# Clock_bord.net
KiCad netlist of a schematic drawn in Altium Designer
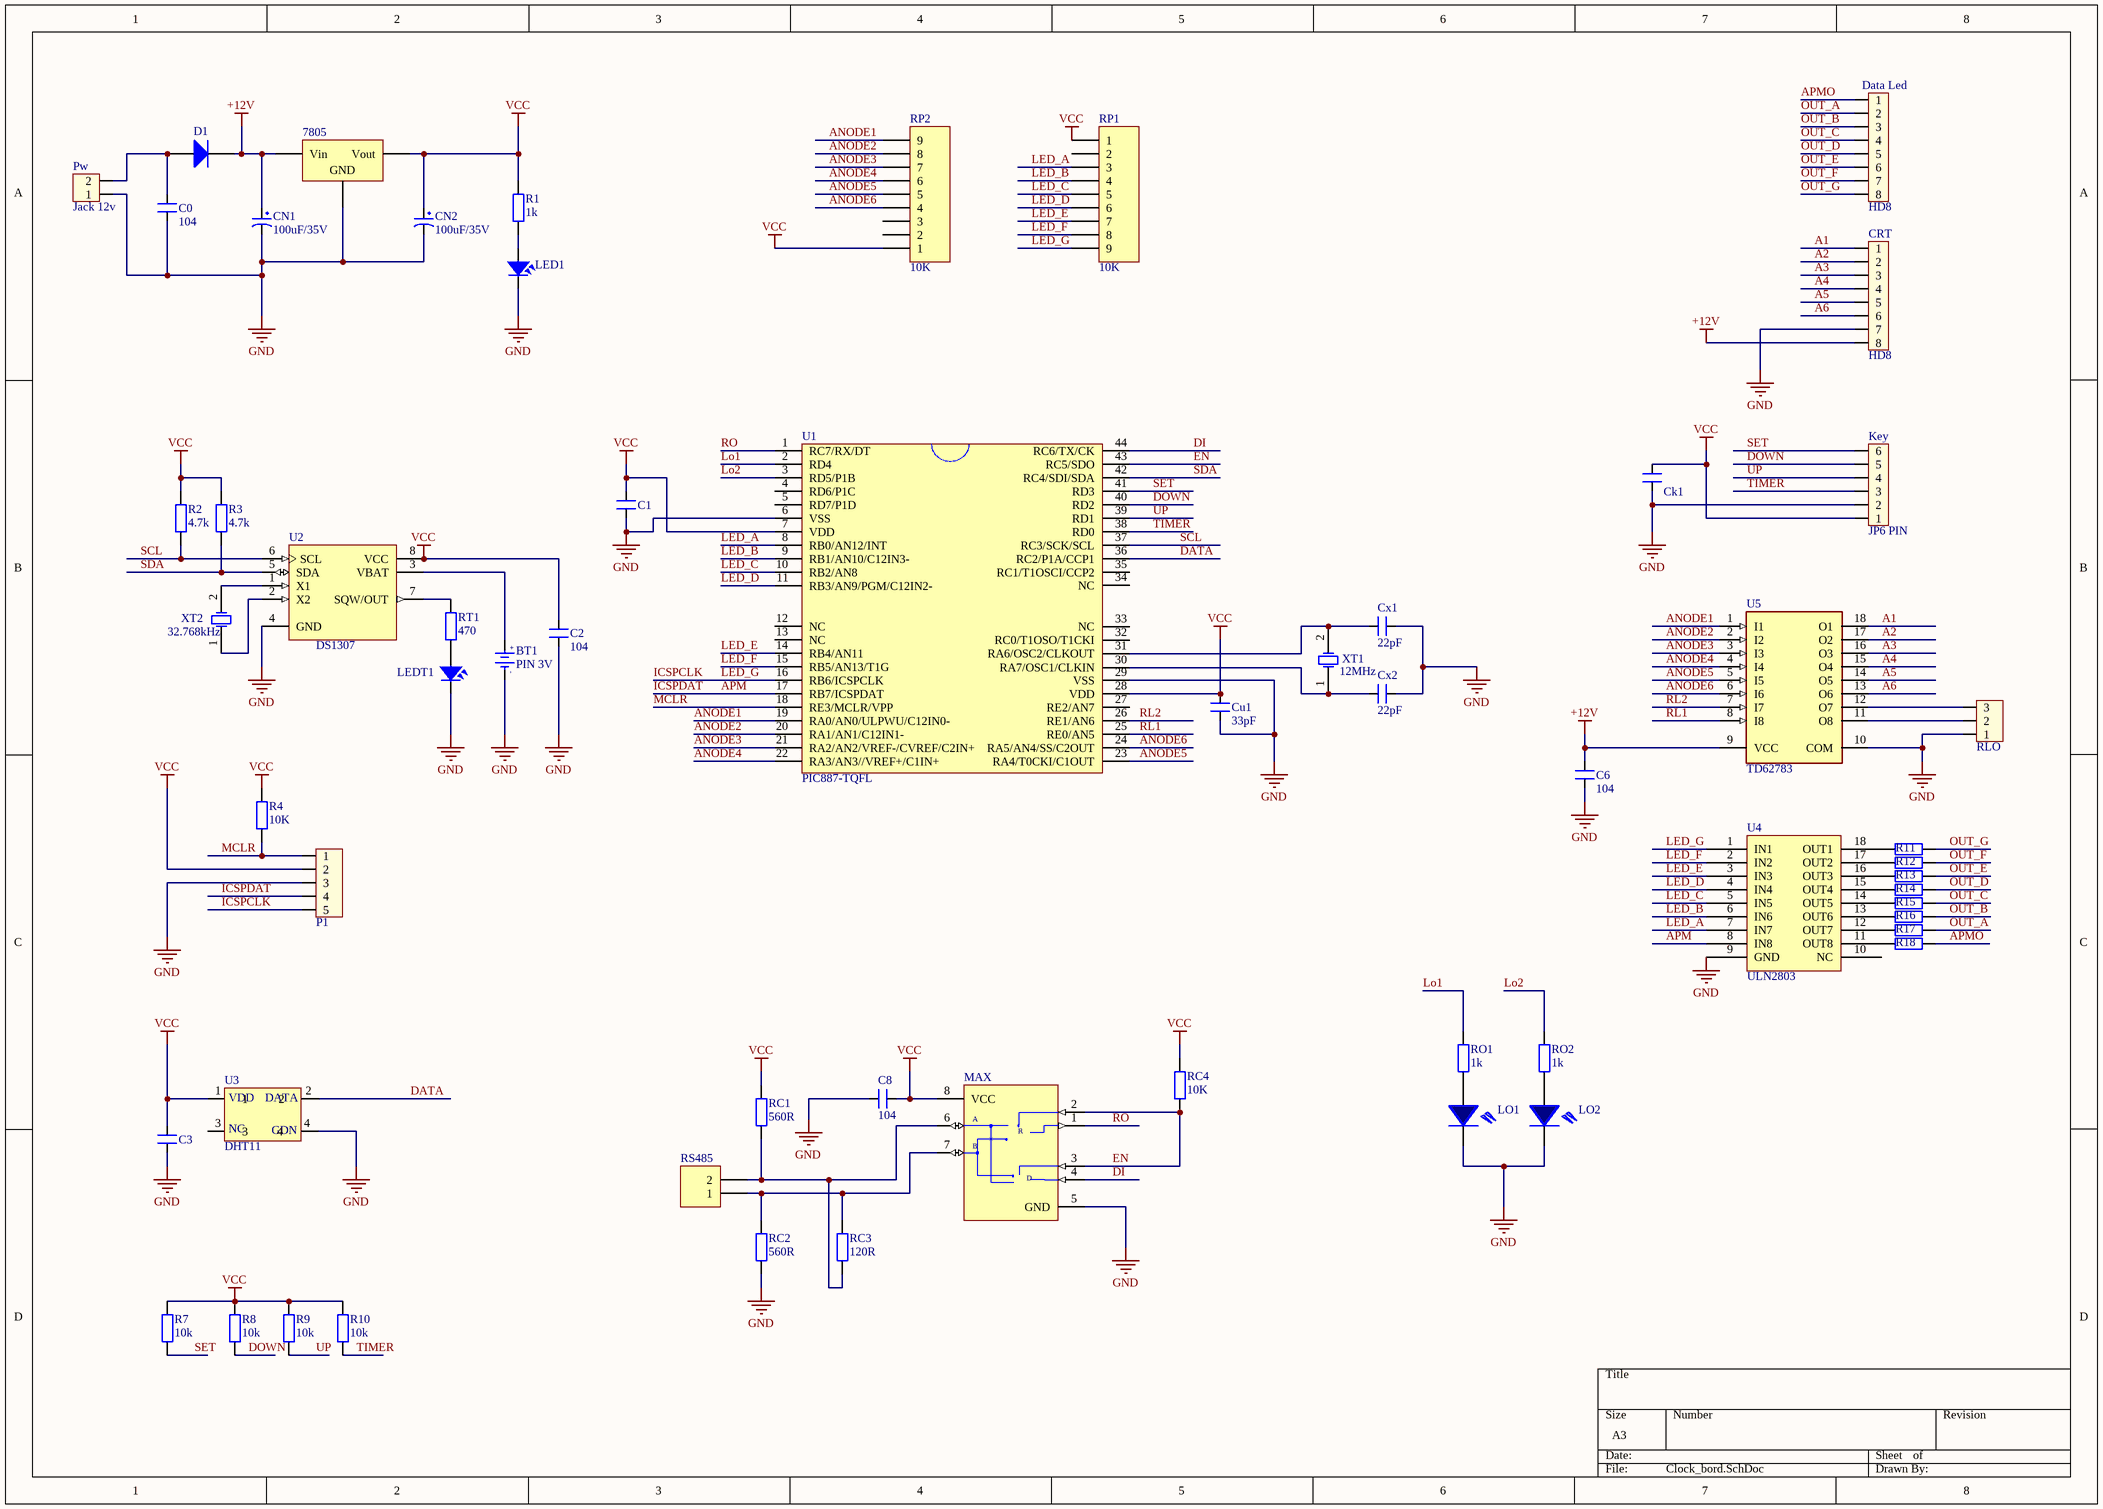
[diagram p0: Clock_bord.SchDoc]

(export (version "E")
  (design (tool "Eeschema 10.0.6"))
  (components
    (comp (ref "7805")
      (value "Volt Reg")
      (footprint "TO-263")
      (description "Voltage Regulator")
      (fields (field (name "PUBLISHER") "Altium Limited"))
      (libsource (lib "Miscellaneous Devices") (part "Volt Reg"))
    )
    (comp (ref "BT1")
      (value "PIN 3V")
      (footprint "Duy_PCB Library:PIN3V")
      (description "Battery 3VDC")
      (libsource (lib "Duy_Schematic") (part "PIN 3V"))
    )
    (comp (ref "C0")
      (value "104")
      (footprint "Duy_PCB Library:CN2")
      (description "Cap np Cremic Value  104pF => 105pF")
      (libsource (lib "Duy_Schematic") (part "CN2"))
    )
    (comp (ref "C1")
      (value "104")
      (footprint "CN1")
      (description "Cap np Cremic Value  104pF => 105pF")
      (libsource (lib "Duy_Schematic") (part "CN2"))
    )
    (comp (ref "C2")
      (value "104")
      (footprint "CN1")
      (description "Cap np Cremic Value  104pF => 105pF")
      (libsource (lib "Duy_Schematic") (part "CN2"))
    )
    (comp (ref "C3")
      (value "104")
      (footprint "CN1")
      (description "Cap np Cremic Value  104pF => 105pF")
      (libsource (lib "Duy_Schematic") (part "CN2"))
    )
    (comp (ref "C6")
      (value "104")
      (footprint "CN1")
      (description "Cap np Cremic Value  104pF => 105pF")
      (libsource (lib "Duy_Schematic") (part "CN2"))
    )
    (comp (ref "C8")
      (value "104")
      (footprint "CN1")
      (description "Cap np Cremic Value  1pF => 472 pF")
      (libsource (lib "Duy_Schematic") (part "CN1"))
    )
    (comp (ref "Ck1")
      (value "100pF")
      (footprint "SM-1206")
      (description "Cap np Cremic Value  1pF => 472 pF")
      (libsource (lib "Duy_Schematic") (part "CN1"))
    )
    (comp (ref "CN1")
      (value "100uF/35V")
      (footprint "CP1.5/3.4")
      (description "Cap 100uF/35V - 470uF/16V")
      (libsource (lib "Duy_Schematic") (part "CP3"))
    )
    (comp (ref "CN2")
      (value "100uF/35V")
      (footprint "CP1.5/3.4")
      (description "Cap 100uF/35V - 470uF/16V")
      (libsource (lib "Duy_Schematic") (part "CP3"))
    )
    (comp (ref "CRT")
      (value "HD8")
      (footprint "HED8")
      (description "Hedear 8")
      (fields (field (name "CREAT BY") "VanDungEvn@Gmail.com"))
      (libsource (lib "Duy_Schematic") (part "Hed8"))
    )
    (comp (ref "Cu1")
      (value "33pF")
      (footprint "SM-0805")
      (description "Cap np Cremic value 1pF => 100pF")
      (libsource (lib "Duy_Schematic") (part "CN0"))
    )
    (comp (ref "Cx1")
      (value "22pF")
      (footprint "CN1")
      (description "Cap np Cremic value 1pF => 100pF")
      (libsource (lib "Duy_Schematic") (part "CN0"))
    )
    (comp (ref "Cx2")
      (value "22pF")
      (footprint "CN1")
      (description "Cap np Cremic value 1pF => 100pF")
      (libsource (lib "Duy_Schematic") (part "CN0"))
    )
    (comp (ref "D1")
      (value "Diode 1N4007")
      (footprint "Duy_PCB Library:D1A")
      (description "1 Amp General Purpose Rectifier")
      (fields (field (name "PUBLISHER") "Altium Limited"))
      (libsource (lib "Miscellaneous Devices") (part "Diode 1N4007"))
    )
    (comp (ref "Data Led")
      (value "HD8")
      (footprint "HED8")
      (description "Hedear 8")
      (fields (field (name "CREAT BY") "VanDungEvn@Gmail.com"))
      (libsource (lib "Duy_Schematic") (part "Hed8"))
    )
    (comp (ref "Key") (value "JP6 PIN") (footprint "JP6") (libsource (lib "Duy_Schematic") (part "JP6")))
    (comp (ref "LED1")
      (value "LED")
      (footprint "SM-1206")
      (description "Led  Vuong")
      (libsource (lib "") (part "LED_1"))
    )
    (comp (ref "LEDT1")
      (value "LED")
      (footprint "SM-1206")
      (description "Led  Vuong")
      (libsource (lib "") (part "LED_1"))
    )
    (comp (ref "LO1")
      (value "LED")
      (footprint "SM-1206")
      (description "Led  Vuong")
      (libsource (lib "Duy_Schematic") (part "LED"))
    )
    (comp (ref "LO2")
      (value "LED")
      (footprint "SM-1206")
      (description "Led  Vuong")
      (libsource (lib "Duy_Schematic") (part "LED"))
    )
    (comp (ref "MAX")
      (value "MAX485CSA")
      (footprint "DIP8/W0.3")
      (description "Low-Power, Slew-Rate-Limited RS-485/RS-422 Transceiver")
      (fields (field (name "PUBLISHER") "Altium Limited"))
      (libsource (lib "Maxim Communication Transceiver") (part "MAX485CSA"))
    )
    (comp (ref "P1")
      (value "JP5")
      (footprint "CON5")
      (description "Connector 5")
      (libsource (lib "Duy_Schematic") (part "Con5"))
    )
    (comp (ref "Pw")
      (value "Jack 12v")
      (footprint "HED2")
      (description "Header 2 (Green)")
      (libsource (lib "Duy_Schematic") (part "Hed2"))
    )
    (comp (ref "R1")
      (value "1k")
      (footprint "SM-1206")
      (description "Resistor 1/4W")
      (libsource (lib "Duy_Schematic") (part "R1/4W"))
    )
    (comp (ref "R2")
      (value "4.7k")
      (footprint "R1/4W")
      (description "Resistor 1/4W")
      (libsource (lib "Duy_Schematic") (part "R1/4W"))
    )
    (comp (ref "R3")
      (value "4.7k")
      (footprint "R1/4W")
      (description "Resistor 1/4W")
      (libsource (lib "Duy_Schematic") (part "R1/4W"))
    )
    (comp (ref "R4")
      (value "10K")
      (footprint "R1/4W")
      (description "Resistor 1/4W")
      (libsource (lib "Duy_Schematic") (part "R1/4W"))
    )
    (comp (ref "R7")
      (value "10k")
      (footprint "R1/4W")
      (description "Resistor 1/4W")
      (libsource (lib "Duy_Schematic") (part "R1/4W"))
    )
    (comp (ref "R8")
      (value "10k")
      (footprint "R1/4W")
      (description "Resistor 1/4W")
      (libsource (lib "Duy_Schematic") (part "R1/4W"))
    )
    (comp (ref "R9")
      (value "10k")
      (footprint "R1/4W")
      (description "Resistor 1/4W")
      (libsource (lib "Duy_Schematic") (part "R1/4W"))
    )
    (comp (ref "R10")
      (value "10k")
      (footprint "R1/4W")
      (description "Resistor 1/4W")
      (libsource (lib "Duy_Schematic") (part "R1/4W"))
    )
    (comp (ref "R11")
      (value "220R")
      (footprint "SM-1206")
      (description "Resistor 1/4W")
      (libsource (lib "Duy_Schematic") (part "R1/4W"))
    )
    (comp (ref "R12")
      (value "220R")
      (footprint "SM-1206")
      (description "Resistor 1/4W")
      (libsource (lib "Duy_Schematic") (part "R1/4W"))
    )
    (comp (ref "R13")
      (value "220R")
      (footprint "SM-1206")
      (description "Resistor 1/4W")
      (libsource (lib "Duy_Schematic") (part "R1/4W"))
    )
    (comp (ref "R14")
      (value "220R")
      (footprint "SM-1206")
      (description "Resistor 1/4W")
      (libsource (lib "Duy_Schematic") (part "R1/4W"))
    )
    (comp (ref "R15")
      (value "220R")
      (footprint "SM-1206")
      (description "Resistor 1/4W")
      (libsource (lib "Duy_Schematic") (part "R1/4W"))
    )
    (comp (ref "R16")
      (value "220R")
      (footprint "SM-1206")
      (description "Resistor 1/4W")
      (libsource (lib "Duy_Schematic") (part "R1/4W"))
    )
    (comp (ref "R17")
      (value "220R")
      (footprint "SM-1206")
      (description "Resistor 1/4W")
      (libsource (lib "Duy_Schematic") (part "R1/4W"))
    )
    (comp (ref "R18")
      (value "220R")
      (footprint "SM-1206")
      (description "Resistor 1/4W")
      (libsource (lib "Duy_Schematic") (part "R1/4W"))
    )
    (comp (ref "RC1")
      (value "560R")
      (footprint "R1/4W")
      (description "Resistor 1/4W")
      (libsource (lib "Duy_Schematic") (part "R1/4W"))
    )
    (comp (ref "RC2")
      (value "560R")
      (footprint "R1/4W")
      (description "Resistor 1/4W")
      (libsource (lib "Duy_Schematic") (part "R1/4W"))
    )
    (comp (ref "RC3")
      (value "120R")
      (footprint "SM-1206")
      (description "Resistor 1/4W")
      (libsource (lib "Duy_Schematic") (part "R1/4W"))
    )
    (comp (ref "RC4")
      (value "10K")
      (footprint "R1/4W")
      (description "Resistor 1/4W")
      (libsource (lib "Duy_Schematic") (part "R1/4W"))
    )
    (comp (ref "RLO")
      (value "JP3")
      (footprint "CON3")
      (description "Connector 3")
      (libsource (lib "Duy_Schematic") (part "Con3"))
    )
    (comp (ref "RO1")
      (value "1k")
      (footprint "SM-1206")
      (description "Resistor 1/4W")
      (libsource (lib "Duy_Schematic") (part "R1/4W"))
    )
    (comp (ref "RO2")
      (value "1k")
      (footprint "SM-1206")
      (description "Resistor 1/4W")
      (libsource (lib "Duy_Schematic") (part "R1/4W"))
    )
    (comp (ref "RP1")
      (value "10K")
      (footprint "RN8")
      (description "Header, 9-Pin")
      (fields (field (name "PUBLISHER") "Altium Limited"))
      (libsource (lib "") (part "Header 9_1"))
    )
    (comp (ref "RP2")
      (value "10K")
      (footprint "RN8")
      (description "Header, 9-Pin")
      (fields (field (name "PUBLISHER") "Altium Limited"))
      (libsource (lib "Miscellaneous Connectors") (part "Header 9"))
    )
    (comp (ref "RS485")
      (value "Header 2")
      (footprint "CON2")
      (description "Header, 2-Pin")
      (fields (field (name "PUBLISHER") "Altium Limited"))
      (libsource (lib "Miscellaneous Connectors") (part "Header 2"))
    )
    (comp (ref "RT1")
      (value "470")
      (footprint "SM-1206")
      (description "Resistor 1/4W")
      (libsource (lib "Duy_Schematic") (part "R1/4W"))
    )
    (comp (ref "U1")
      (value "PIC887-TQFL")
      (footprint "TQFP-44")
      (description "16F887_TQFP")
      (libsource (lib "Duy_Schematic") (part "PIC16F887-TQFL"))
    )
    (comp (ref "U2")
      (value "DS1307")
      (footprint "DIP8/W0.3")
      (description "64 X 8 Serial Real-Time Clock")
      (fields (field (name "PUBLISHER") "Altium Limited"))
      (libsource (lib "Dallas Peripheral Real Time Clock") (part "DS1307"))
    )
    (comp (ref "U3")
      (value "DHT11")
      (footprint "CON4")
      (description "Sensor Ther")
      (libsource (lib "Duy_Schematic") (part "DHT11"))
    )
    (comp (ref "U4") (value "ULN2803") (footprint "ULN2803") (libsource (lib "Device") (part "ULN 2803")))
    (comp (ref "U5")
      (value "TD62783")
      (footprint "ULN2803")
      (libsource (lib "Duy_Schematic") (part "TD62783AF"))
    )
    (comp (ref "XT1")
      (value "12MHz")
      (footprint "Xtal_SMD")
      (description "Crystal Oscillator")
      (fields (field (name "PUBLISHER") "Altium Limited"))
      (libsource (lib "Miscellaneous Devices") (part "XTAL"))
    )
    (comp (ref "XT2")
      (value "32.768kHz")
      (footprint "Device:tu_gom")
      (description "Crystal Oscillator")
      (fields (field (name "PUBLISHER") "Altium Limited"))
      (libsource (lib "Miscellaneous Devices") (part "XTAL"))
    )
  )
  (nets
    (net (code "1") (name "+12V") (class "Default")
      (node (ref "7805") (pin "1") (pinfunction "Vin_1") (pintype "passive"))
      (node (ref "C6") (pin "2") (pinfunction "2_2") (pintype "passive"))
      (node (ref "CN1") (pin "1") (pinfunction "1_1") (pintype "passive"))
      (node (ref "CRT") (pin "8") (pinfunction "8_8") (pintype "passive"))
      (node (ref "D1") (pin "2") (pinfunction "K_2") (pintype "passive"))
      (node (ref "U5") (pin "9") (pinfunction "VCC_9") (pintype "power_in"))
    )
    (net (code "2") (name "/A1") (class "Default")
      (node (ref "CRT") (pin "1") (pinfunction "1_1") (pintype "passive"))
      (node (ref "U5") (pin "18") (pinfunction "O1_18") (pintype "open_collector"))
    )
    (net (code "3") (name "/A2") (class "Default")
      (node (ref "CRT") (pin "2") (pinfunction "2_2") (pintype "passive"))
      (node (ref "U5") (pin "17") (pinfunction "O2_17") (pintype "open_collector"))
    )
    (net (code "4") (name "/A3") (class "Default")
      (node (ref "CRT") (pin "3") (pinfunction "3_3") (pintype "passive"))
      (node (ref "U5") (pin "16") (pinfunction "O3_16") (pintype "open_collector"))
    )
    (net (code "5") (name "/A4") (class "Default")
      (node (ref "CRT") (pin "4") (pinfunction "4_4") (pintype "passive"))
      (node (ref "U5") (pin "15") (pinfunction "O4_15") (pintype "open_collector"))
    )
    (net (code "6") (name "/A5") (class "Default")
      (node (ref "CRT") (pin "5") (pinfunction "5_5") (pintype "passive"))
      (node (ref "U5") (pin "14") (pinfunction "O5_14") (pintype "open_collector"))
    )
    (net (code "7") (name "/A6") (class "Default")
      (node (ref "CRT") (pin "6") (pinfunction "6_6") (pintype "passive"))
      (node (ref "U5") (pin "13") (pinfunction "O6_13") (pintype "open_collector"))
    )
    (net (code "8") (name "/ANODE1") (class "Default")
      (node (ref "RP2") (pin "9") (pinfunction "9_9") (pintype "passive"))
      (node (ref "U1") (pin "19") (pinfunction "RA0/AN0/ULPWU/C12IN0-_19") (pintype "passive"))
      (node (ref "U5") (pin "1") (pinfunction "I1_1") (pintype "input"))
    )
    (net (code "9") (name "/ANODE2") (class "Default")
      (node (ref "RP2") (pin "8") (pinfunction "8_8") (pintype "passive"))
      (node (ref "U1") (pin "20") (pinfunction "RA1/AN1/C12IN1-_20") (pintype "passive"))
      (node (ref "U5") (pin "2") (pinfunction "I2_2") (pintype "input"))
    )
    (net (code "10") (name "/ANODE3") (class "Default")
      (node (ref "RP2") (pin "7") (pinfunction "7_7") (pintype "passive"))
      (node (ref "U1") (pin "21") (pinfunction "RA2/AN2/VREF-/CVREF/C2IN+_21") (pintype "passive"))
      (node (ref "U5") (pin "3") (pinfunction "I3_3") (pintype "input"))
    )
    (net (code "11") (name "/ANODE4") (class "Default")
      (node (ref "RP2") (pin "6") (pinfunction "6_6") (pintype "passive"))
      (node (ref "U1") (pin "22") (pinfunction "RA3/AN3//VREF+/C1IN+_22") (pintype "passive"))
      (node (ref "U5") (pin "4") (pinfunction "I4_4") (pintype "input"))
    )
    (net (code "12") (name "/ANODE5") (class "Default")
      (node (ref "RP2") (pin "5") (pinfunction "5_5") (pintype "passive"))
      (node (ref "U1") (pin "23") (pinfunction "RA4/T0CKI/C1OUT_23") (pintype "passive"))
      (node (ref "U5") (pin "5") (pinfunction "I5_5") (pintype "input"))
    )
    (net (code "13") (name "/ANODE6") (class "Default")
      (node (ref "RP2") (pin "4") (pinfunction "4_4") (pintype "passive"))
      (node (ref "U1") (pin "24") (pinfunction "RA5/AN4/SS/C2OUT_24") (pintype "passive"))
      (node (ref "U5") (pin "6") (pinfunction "I6_6") (pintype "input"))
    )
    (net (code "14") (name "/APM") (class "Default")
      (node (ref "P1") (pin "4") (pinfunction "4_4") (pintype "passive"))
      (node (ref "U1") (pin "17") (pinfunction "RB7/ICSPDAT_17") (pintype "passive"))
      (node (ref "U4") (pin "8") (pinfunction "IN8_8") (pintype "passive"))
    )
    (net (code "15") (name "/APMO") (class "Default")
      (node (ref "Data Led") (pin "1") (pinfunction "1_1") (pintype "passive"))
      (node (ref "R18") (pin "2") (pinfunction "2_2") (pintype "passive"))
    )
    (net (code "16") (name "/DATA") (class "Default")
      (node (ref "U1") (pin "36") (pinfunction "RC2/P1A/CCP1_36") (pintype "passive"))
      (node (ref "U3") (pin "2") (pinfunction "2_2") (pintype "passive"))
    )
    (net (code "17") (name "/DI") (class "Default")
      (node (ref "MAX") (pin "4") (pinfunction "DI_4") (pintype "input"))
      (node (ref "U1") (pin "44") (pinfunction "RC6/TX/CK_44") (pintype "passive"))
    )
    (net (code "18") (name "/DOWN") (class "Default")
      (node (ref "Key") (pin "5") (pinfunction "5_5") (pintype "passive"))
      (node (ref "R8") (pin "1") (pinfunction "1_1") (pintype "passive"))
      (node (ref "U1") (pin "40") (pinfunction "RD2_40") (pintype "passive"))
    )
    (net (code "19") (name "/EN") (class "Default")
      (node (ref "MAX") (pin "2") (pinfunction "~{RE}_2") (pintype "input"))
      (node (ref "MAX") (pin "3") (pinfunction "DE_3") (pintype "input"))
      (node (ref "RC4") (pin "1") (pinfunction "1_1") (pintype "passive"))
      (node (ref "U1") (pin "43") (pinfunction "RC5/SDO_43") (pintype "passive"))
    )
    (net (code "20") (name "/ICSPCLK") (class "Default")
      (node (ref "P1") (pin "5") (pinfunction "5_5") (pintype "passive"))
      (node (ref "RP1") (pin "9") (pinfunction "9_9") (pintype "passive"))
      (node (ref "U1") (pin "16") (pinfunction "RB6/ICSPCLK_16") (pintype "passive"))
      (node (ref "U4") (pin "1") (pinfunction "IN1_1") (pintype "passive"))
    )
    (net (code "21") (name "/LED_A") (class "Default")
      (node (ref "RP1") (pin "3") (pinfunction "3_3") (pintype "passive"))
      (node (ref "U1") (pin "8") (pinfunction "RB0/AN12/INT_8") (pintype "passive"))
      (node (ref "U4") (pin "7") (pinfunction "IN7_7") (pintype "passive"))
    )
    (net (code "22") (name "/LED_B") (class "Default")
      (node (ref "RP1") (pin "4") (pinfunction "4_4") (pintype "passive"))
      (node (ref "U1") (pin "9") (pinfunction "RB1/AN10/C12IN3-_9") (pintype "passive"))
      (node (ref "U4") (pin "6") (pinfunction "IN6_6") (pintype "passive"))
    )
    (net (code "23") (name "/LED_C") (class "Default")
      (node (ref "RP1") (pin "5") (pinfunction "5_5") (pintype "passive"))
      (node (ref "U1") (pin "10") (pinfunction "RB2/AN8_10") (pintype "passive"))
      (node (ref "U4") (pin "5") (pinfunction "IN5_5") (pintype "passive"))
    )
    (net (code "24") (name "/LED_D") (class "Default")
      (node (ref "RP1") (pin "6") (pinfunction "6_6") (pintype "passive"))
      (node (ref "U1") (pin "11") (pinfunction "RB3/AN9/PGM/C12IN2-_11") (pintype "passive"))
      (node (ref "U4") (pin "4") (pinfunction "IN4_4") (pintype "passive"))
    )
    (net (code "25") (name "/LED_E") (class "Default")
      (node (ref "RP1") (pin "7") (pinfunction "7_7") (pintype "passive"))
      (node (ref "U1") (pin "14") (pinfunction "RB4/AN11_14") (pintype "passive"))
      (node (ref "U4") (pin "3") (pinfunction "IN3_3") (pintype "passive"))
    )
    (net (code "26") (name "/LED_F") (class "Default")
      (node (ref "RP1") (pin "8") (pinfunction "8_8") (pintype "passive"))
      (node (ref "U1") (pin "15") (pinfunction "RB5/AN13/T1G_15") (pintype "passive"))
      (node (ref "U4") (pin "2") (pinfunction "IN2_2") (pintype "passive"))
    )
    (net (code "27") (name "/Lo1") (class "Default")
      (node (ref "RO1") (pin "1") (pinfunction "1_1") (pintype "passive"))
      (node (ref "U1") (pin "2") (pinfunction "RD4_2") (pintype "passive"))
    )
    (net (code "28") (name "/Lo2") (class "Default")
      (node (ref "RO2") (pin "1") (pinfunction "1_1") (pintype "passive"))
      (node (ref "U1") (pin "3") (pinfunction "RD5/P1B_3") (pintype "passive"))
    )
    (net (code "29") (name "/MCLR") (class "Default")
      (node (ref "P1") (pin "1") (pinfunction "1_1") (pintype "passive"))
      (node (ref "R4") (pin "1") (pinfunction "1_1") (pintype "passive"))
      (node (ref "U1") (pin "18") (pinfunction "RE3/MCLR/VPP_18") (pintype "passive"))
    )
    (net (code "30") (name "/OUT_A") (class "Default")
      (node (ref "Data Led") (pin "2") (pinfunction "2_2") (pintype "passive"))
      (node (ref "R17") (pin "2") (pinfunction "2_2") (pintype "passive"))
    )
    (net (code "31") (name "/OUT_B") (class "Default")
      (node (ref "Data Led") (pin "3") (pinfunction "3_3") (pintype "passive"))
      (node (ref "R16") (pin "2") (pinfunction "2_2") (pintype "passive"))
    )
    (net (code "32") (name "/OUT_C") (class "Default")
      (node (ref "Data Led") (pin "4") (pinfunction "4_4") (pintype "passive"))
      (node (ref "R15") (pin "2") (pinfunction "2_2") (pintype "passive"))
    )
    (net (code "33") (name "/OUT_D") (class "Default")
      (node (ref "Data Led") (pin "5") (pinfunction "5_5") (pintype "passive"))
      (node (ref "R14") (pin "2") (pinfunction "2_2") (pintype "passive"))
    )
    (net (code "34") (name "/OUT_E") (class "Default")
      (node (ref "Data Led") (pin "6") (pinfunction "6_6") (pintype "passive"))
      (node (ref "R13") (pin "2") (pinfunction "2_2") (pintype "passive"))
    )
    (net (code "35") (name "/OUT_F") (class "Default")
      (node (ref "Data Led") (pin "7") (pinfunction "7_7") (pintype "passive"))
      (node (ref "R12") (pin "2") (pinfunction "2_2") (pintype "passive"))
    )
    (net (code "36") (name "/OUT_G") (class "Default")
      (node (ref "Data Led") (pin "8") (pinfunction "8_8") (pintype "passive"))
      (node (ref "R11") (pin "2") (pinfunction "2_2") (pintype "passive"))
    )
    (net (code "37") (name "/RL1") (class "Default")
      (node (ref "U1") (pin "25") (pinfunction "RE0/AN5_25") (pintype "passive"))
      (node (ref "U5") (pin "8") (pinfunction "I8_8") (pintype "input"))
    )
    (net (code "38") (name "/RL2") (class "Default")
      (node (ref "U1") (pin "26") (pinfunction "RE1/AN6_26") (pintype "passive"))
      (node (ref "U5") (pin "7") (pinfunction "I7_7") (pintype "input"))
    )
    (net (code "39") (name "/RO") (class "Default")
      (node (ref "MAX") (pin "1") (pinfunction "RO_1") (pintype "output"))
      (node (ref "U1") (pin "1") (pinfunction "RC7/RX/DT_1") (pintype "passive"))
    )
    (net (code "40") (name "/SCL") (class "Default")
      (node (ref "R2") (pin "1") (pinfunction "1_1") (pintype "passive"))
      (node (ref "U1") (pin "37") (pinfunction "RC3/SCK/SCL_37") (pintype "passive"))
      (node (ref "U2") (pin "6") (pinfunction "SCL_6") (pintype "input"))
    )
    (net (code "41") (name "/SDA") (class "Default")
      (node (ref "R3") (pin "1") (pinfunction "1_1") (pintype "passive"))
      (node (ref "U1") (pin "42") (pinfunction "RC4/SDI/SDA_42") (pintype "passive"))
      (node (ref "U2") (pin "5") (pinfunction "SDA_5") (pintype "bidirectional"))
    )
    (net (code "42") (name "/SET") (class "Default")
      (node (ref "Key") (pin "6") (pinfunction "6_6") (pintype "passive"))
      (node (ref "R7") (pin "1") (pinfunction "1_1") (pintype "passive"))
      (node (ref "U1") (pin "41") (pinfunction "RD3_41") (pintype "passive"))
    )
    (net (code "43") (name "/TIMER") (class "Default")
      (node (ref "Key") (pin "3") (pinfunction "3_3") (pintype "passive"))
      (node (ref "R10") (pin "1") (pinfunction "1_1") (pintype "passive"))
      (node (ref "U1") (pin "38") (pinfunction "RD0_38") (pintype "passive"))
    )
    (net (code "44") (name "/UP") (class "Default")
      (node (ref "Key") (pin "4") (pinfunction "4_4") (pintype "passive"))
      (node (ref "R9") (pin "1") (pinfunction "1_1") (pintype "passive"))
      (node (ref "U1") (pin "39") (pinfunction "RD1_39") (pintype "passive"))
    )
    (net (code "45") (name "GND") (class "Default")
      (node (ref "7805") (pin "2") (pinfunction "GND_2") (pintype "passive"))
      (node (ref "BT1") (pin "2") (pinfunction "GND_2") (pintype "passive"))
      (node (ref "C0") (pin "1") (pinfunction "1_1") (pintype "passive"))
      (node (ref "C1") (pin "1") (pinfunction "1_1") (pintype "passive"))
      (node (ref "C2") (pin "1") (pinfunction "1_1") (pintype "passive"))
      (node (ref "C3") (pin "1") (pinfunction "1_1") (pintype "passive"))
      (node (ref "C6") (pin "1") (pinfunction "1_1") (pintype "passive"))
      (node (ref "C8") (pin "1") (pinfunction "1_1") (pintype "passive"))
      (node (ref "CN1") (pin "2") (pinfunction "2_2") (pintype "passive"))
      (node (ref "CN2") (pin "2") (pinfunction "2_2") (pintype "passive"))
      (node (ref "CRT") (pin "7") (pinfunction "7_7") (pintype "passive"))
      (node (ref "Ck1") (pin "1") (pinfunction "1_1") (pintype "passive"))
      (node (ref "Cu1") (pin "1") (pinfunction "1_1") (pintype "passive"))
      (node (ref "Cx1") (pin "2") (pinfunction "2_2") (pintype "passive"))
      (node (ref "Cx2") (pin "2") (pinfunction "2_2") (pintype "passive"))
      (node (ref "Key") (pin "2") (pinfunction "2_2") (pintype "passive"))
      (node (ref "LED1") (pin "2") (pinfunction "2_2") (pintype "passive"))
      (node (ref "LEDT1") (pin "2") (pinfunction "2_2") (pintype "passive"))
      (node (ref "LO1") (pin "2") (pinfunction "2_2") (pintype "passive"))
      (node (ref "LO2") (pin "2") (pinfunction "2_2") (pintype "passive"))
      (node (ref "MAX") (pin "5") (pinfunction "GND_5") (pintype "power_in"))
      (node (ref "P1") (pin "3") (pinfunction "3_3") (pintype "passive"))
      (node (ref "Pw") (pin "1") (pinfunction "1_1") (pintype "passive"))
      (node (ref "RC2") (pin "1") (pinfunction "1_1") (pintype "passive"))
      (node (ref "RLO") (pin "1") (pinfunction "1_1") (pintype "passive"))
      (node (ref "U1") (pin "29") (pinfunction "VSS_29") (pintype "passive"))
      (node (ref "U1") (pin "6") (pinfunction "VSS_6") (pintype "passive"))
      (node (ref "U2") (pin "4") (pinfunction "GND_4") (pintype "power_in"))
      (node (ref "U3") (pin "4") (pinfunction "4_4") (pintype "passive"))
      (node (ref "U4") (pin "9") (pinfunction "GND_9") (pintype "passive"))
      (node (ref "U5") (pin "10") (pinfunction "COM_10") (pintype "passive"))
    )
    (net (code "46") (name "Net-(BT1-+3V)") (class "Default")
      (node (ref "BT1") (pin "1") (pinfunction "+3V_1") (pintype "passive"))
      (node (ref "U2") (pin "3") (pinfunction "VBAT_3") (pintype "power_in"))
    )
    (net (code "47") (name "Net-(D1-A)") (class "Default")
      (node (ref "C0") (pin "2") (pinfunction "2_2") (pintype "passive"))
      (node (ref "D1") (pin "1") (pinfunction "A_1") (pintype "passive"))
      (node (ref "Pw") (pin "2") (pinfunction "2_2") (pintype "passive"))
    )
    (net (code "48") (name "Net-(LED1-Pad1)") (class "Default")
      (node (ref "LED1") (pin "1") (pinfunction "1_1") (pintype "passive"))
      (node (ref "R1") (pin "1") (pinfunction "1_1") (pintype "passive"))
    )
    (net (code "49") (name "Net-(LEDT1-Pad1)") (class "Default")
      (node (ref "LEDT1") (pin "1") (pinfunction "1_1") (pintype "passive"))
      (node (ref "RT1") (pin "1") (pinfunction "1_1") (pintype "passive"))
    )
    (net (code "50") (name "Net-(LO1-Pad1)") (class "Default")
      (node (ref "LO1") (pin "1") (pinfunction "1_1") (pintype "passive"))
      (node (ref "RO1") (pin "2") (pinfunction "2_2") (pintype "passive"))
    )
    (net (code "51") (name "Net-(LO2-Pad1)") (class "Default")
      (node (ref "LO2") (pin "1") (pinfunction "1_1") (pintype "passive"))
      (node (ref "RO2") (pin "2") (pinfunction "2_2") (pintype "passive"))
    )
    (net (code "52") (name "Net-(MAX-A)") (class "Default")
      (node (ref "MAX") (pin "6") (pinfunction "A_6") (pintype "bidirectional"))
      (node (ref "RC1") (pin "1") (pinfunction "1_1") (pintype "passive"))
      (node (ref "RC3") (pin "1") (pinfunction "1_1") (pintype "passive"))
      (node (ref "RS485") (pin "2") (pinfunction "2_2") (pintype "passive"))
    )
    (net (code "53") (name "Net-(MAX-B)") (class "Default")
      (node (ref "MAX") (pin "7") (pinfunction "B_7") (pintype "bidirectional"))
      (node (ref "RC2") (pin "2") (pinfunction "2_2") (pintype "passive"))
      (node (ref "RC3") (pin "2") (pinfunction "2_2") (pintype "passive"))
      (node (ref "RS485") (pin "1") (pinfunction "1_1") (pintype "passive"))
    )
    (net (code "54") (name "Net-(U1-RA6{slash}OSC2{slash}CLKOUT)") (class "Default")
      (node (ref "Cx1") (pin "1") (pinfunction "1_1") (pintype "passive"))
      (node (ref "U1") (pin "31") (pinfunction "RA6/OSC2/CLKOUT_31") (pintype "passive"))
      (node (ref "XT1") (pin "2") (pinfunction "OSC2_2") (pintype "passive"))
    )
    (net (code "55") (name "Net-(U1-RA7{slash}OSC1{slash}CLKIN)") (class "Default")
      (node (ref "Cx2") (pin "1") (pinfunction "1_1") (pintype "passive"))
      (node (ref "U1") (pin "30") (pinfunction "RA7/OSC1/CLKIN_30") (pintype "passive"))
      (node (ref "XT1") (pin "1") (pinfunction "OSC1_1") (pintype "passive"))
    )
    (net (code "56") (name "Net-(U2-SQW{slash}OUT)") (class "Default")
      (node (ref "RT1") (pin "2") (pinfunction "2_2") (pintype "passive"))
      (node (ref "U2") (pin "7") (pinfunction "SQW/OUT_7") (pintype "output"))
    )
    (net (code "57") (name "Net-(U2-X1)") (class "Default")
      (node (ref "U2") (pin "1") (pinfunction "X1_1") (pintype "input"))
      (node (ref "XT2") (pin "2") (pinfunction "OSC2_2") (pintype "passive"))
    )
    (net (code "58") (name "Net-(U2-X2)") (class "Default")
      (node (ref "U2") (pin "2") (pinfunction "X2_2") (pintype "input"))
      (node (ref "XT2") (pin "1") (pinfunction "OSC1_1") (pintype "passive"))
    )
    (net (code "59") (name "Net-(U4-OUT1)") (class "Default")
      (node (ref "R11") (pin "1") (pinfunction "1_1") (pintype "passive"))
      (node (ref "U4") (pin "18") (pinfunction "OUT1_18") (pintype "passive"))
    )
    (net (code "60") (name "Net-(U4-OUT2)") (class "Default")
      (node (ref "R12") (pin "1") (pinfunction "1_1") (pintype "passive"))
      (node (ref "U4") (pin "17") (pinfunction "OUT2_17") (pintype "passive"))
    )
    (net (code "61") (name "Net-(U4-OUT3)") (class "Default")
      (node (ref "R13") (pin "1") (pinfunction "1_1") (pintype "passive"))
      (node (ref "U4") (pin "16") (pinfunction "OUT3_16") (pintype "passive"))
    )
    (net (code "62") (name "Net-(U4-OUT4)") (class "Default")
      (node (ref "R14") (pin "1") (pinfunction "1_1") (pintype "passive"))
      (node (ref "U4") (pin "15") (pinfunction "OUT4_15") (pintype "passive"))
    )
    (net (code "63") (name "Net-(U4-OUT5)") (class "Default")
      (node (ref "R15") (pin "1") (pinfunction "1_1") (pintype "passive"))
      (node (ref "U4") (pin "14") (pinfunction "OUT5_14") (pintype "passive"))
    )
    (net (code "64") (name "Net-(U4-OUT6)") (class "Default")
      (node (ref "R16") (pin "1") (pinfunction "1_1") (pintype "passive"))
      (node (ref "U4") (pin "13") (pinfunction "OUT6_13") (pintype "passive"))
    )
    (net (code "65") (name "Net-(U4-OUT7)") (class "Default")
      (node (ref "R17") (pin "1") (pinfunction "1_1") (pintype "passive"))
      (node (ref "U4") (pin "12") (pinfunction "OUT7_12") (pintype "passive"))
    )
    (net (code "66") (name "Net-(U4-OUT8)") (class "Default")
      (node (ref "R18") (pin "1") (pinfunction "1_1") (pintype "passive"))
      (node (ref "U4") (pin "11") (pinfunction "OUT8_11") (pintype "passive"))
    )
    (net (code "67") (name "Net-(U5-O7)") (class "Default")
      (node (ref "RLO") (pin "3") (pinfunction "3_3") (pintype "passive"))
      (node (ref "U5") (pin "12") (pinfunction "O7_12") (pintype "open_collector"))
    )
    (net (code "68") (name "Net-(U5-O8)") (class "Default")
      (node (ref "RLO") (pin "2") (pinfunction "2_2") (pintype "passive"))
      (node (ref "U5") (pin "11") (pinfunction "O8_11") (pintype "open_collector"))
    )
    (net (code "69") (name "VCC") (class "Default")
      (node (ref "7805") (pin "3") (pinfunction "Vout_3") (pintype "passive"))
      (node (ref "C1") (pin "2") (pinfunction "2_2") (pintype "passive"))
      (node (ref "C2") (pin "2") (pinfunction "2_2") (pintype "passive"))
      (node (ref "C3") (pin "2") (pinfunction "2_2") (pintype "passive"))
      (node (ref "C8") (pin "2") (pinfunction "2_2") (pintype "passive"))
      (node (ref "CN2") (pin "1") (pinfunction "1_1") (pintype "passive"))
      (node (ref "Ck1") (pin "2") (pinfunction "2_2") (pintype "passive"))
      (node (ref "Cu1") (pin "2") (pinfunction "2_2") (pintype "passive"))
      (node (ref "Key") (pin "1") (pinfunction "1_1") (pintype "passive"))
      (node (ref "MAX") (pin "8") (pinfunction "VCC_8") (pintype "power_in"))
      (node (ref "P1") (pin "2") (pinfunction "2_2") (pintype "passive"))
      (node (ref "R1") (pin "2") (pinfunction "2_2") (pintype "passive"))
      (node (ref "R10") (pin "2") (pinfunction "2_2") (pintype "passive"))
      (node (ref "R2") (pin "2") (pinfunction "2_2") (pintype "passive"))
      (node (ref "R3") (pin "2") (pinfunction "2_2") (pintype "passive"))
      (node (ref "R4") (pin "2") (pinfunction "2_2") (pintype "passive"))
      (node (ref "R7") (pin "2") (pinfunction "2_2") (pintype "passive"))
      (node (ref "R8") (pin "2") (pinfunction "2_2") (pintype "passive"))
      (node (ref "R9") (pin "2") (pinfunction "2_2") (pintype "passive"))
      (node (ref "RC1") (pin "2") (pinfunction "2_2") (pintype "passive"))
      (node (ref "RC4") (pin "2") (pinfunction "2_2") (pintype "passive"))
      (node (ref "RP1") (pin "1") (pinfunction "1_1") (pintype "passive"))
      (node (ref "RP2") (pin "1") (pinfunction "1_1") (pintype "passive"))
      (node (ref "U1") (pin "28") (pinfunction "VDD_28") (pintype "passive"))
      (node (ref "U1") (pin "7") (pinfunction "VDD_7") (pintype "passive"))
      (node (ref "U2") (pin "8") (pinfunction "VCC_8") (pintype "power_in"))
      (node (ref "U3") (pin "1") (pinfunction "1_1") (pintype "passive"))
    )
    (net (code "70") (name "unconnected-(RP1-Pad2)") (class "Default")
      (node (ref "RP1") (pin "2") (pinfunction "2_2") (pintype "passive"))
    )
    (net (code "71") (name "unconnected-(RP2-Pad2)") (class "Default")
      (node (ref "RP2") (pin "2") (pinfunction "2_2") (pintype "passive"))
    )
    (net (code "72") (name "unconnected-(RP2-Pad3)") (class "Default")
      (node (ref "RP2") (pin "3") (pinfunction "3_3") (pintype "passive"))
    )
    (net (code "73") (name "unconnected-(U1-NC-Pad12)") (class "Default")
      (node (ref "U1") (pin "12") (pinfunction "NC_12") (pintype "passive"))
    )
    (net (code "74") (name "unconnected-(U1-NC-Pad13)") (class "Default")
      (node (ref "U1") (pin "13") (pinfunction "NC_13") (pintype "passive"))
    )
    (net (code "75") (name "unconnected-(U1-NC-Pad33)") (class "Default")
      (node (ref "U1") (pin "33") (pinfunction "NC_33") (pintype "passive"))
    )
    (net (code "76") (name "unconnected-(U1-NC-Pad34)") (class "Default")
      (node (ref "U1") (pin "34") (pinfunction "NC_34") (pintype "passive"))
    )
    (net (code "77") (name "unconnected-(U1-RC0{slash}T1OSO{slash}T1CKI-Pad32)") (class "Default")
      (node (ref "U1") (pin "32") (pinfunction "RC0/T1OSO/T1CKI_32") (pintype "passive"))
    )
    (net (code "78") (name "unconnected-(U1-RC1{slash}T1OSCI{slash}CCP2-Pad35)") (class "Default")
      (node (ref "U1") (pin "35") (pinfunction "RC1/T1OSCI/CCP2_35") (pintype "passive"))
    )
    (net (code "79") (name "unconnected-(U1-RD6{slash}P1C-Pad4)") (class "Default")
      (node (ref "U1") (pin "4") (pinfunction "RD6/P1C_4") (pintype "passive"))
    )
    (net (code "80") (name "unconnected-(U1-RD7{slash}P1D-Pad5)") (class "Default")
      (node (ref "U1") (pin "5") (pinfunction "RD7/P1D_5") (pintype "passive"))
    )
    (net (code "81") (name "unconnected-(U1-RE2{slash}AN7-Pad27)") (class "Default")
      (node (ref "U1") (pin "27") (pinfunction "RE2/AN7_27") (pintype "passive"))
    )
    (net (code "82") (name "unconnected-(U3-Pad3)") (class "Default")
      (node (ref "U3") (pin "3") (pinfunction "3_3") (pintype "passive"))
    )
    (net (code "83") (name "unconnected-(U4-NC-Pad10)") (class "Default")
      (node (ref "U4") (pin "10") (pinfunction "NC_10") (pintype "passive"))
    )
  )
)
